# moc.net
KiCad netlist of a schematic drawn in EAGLE
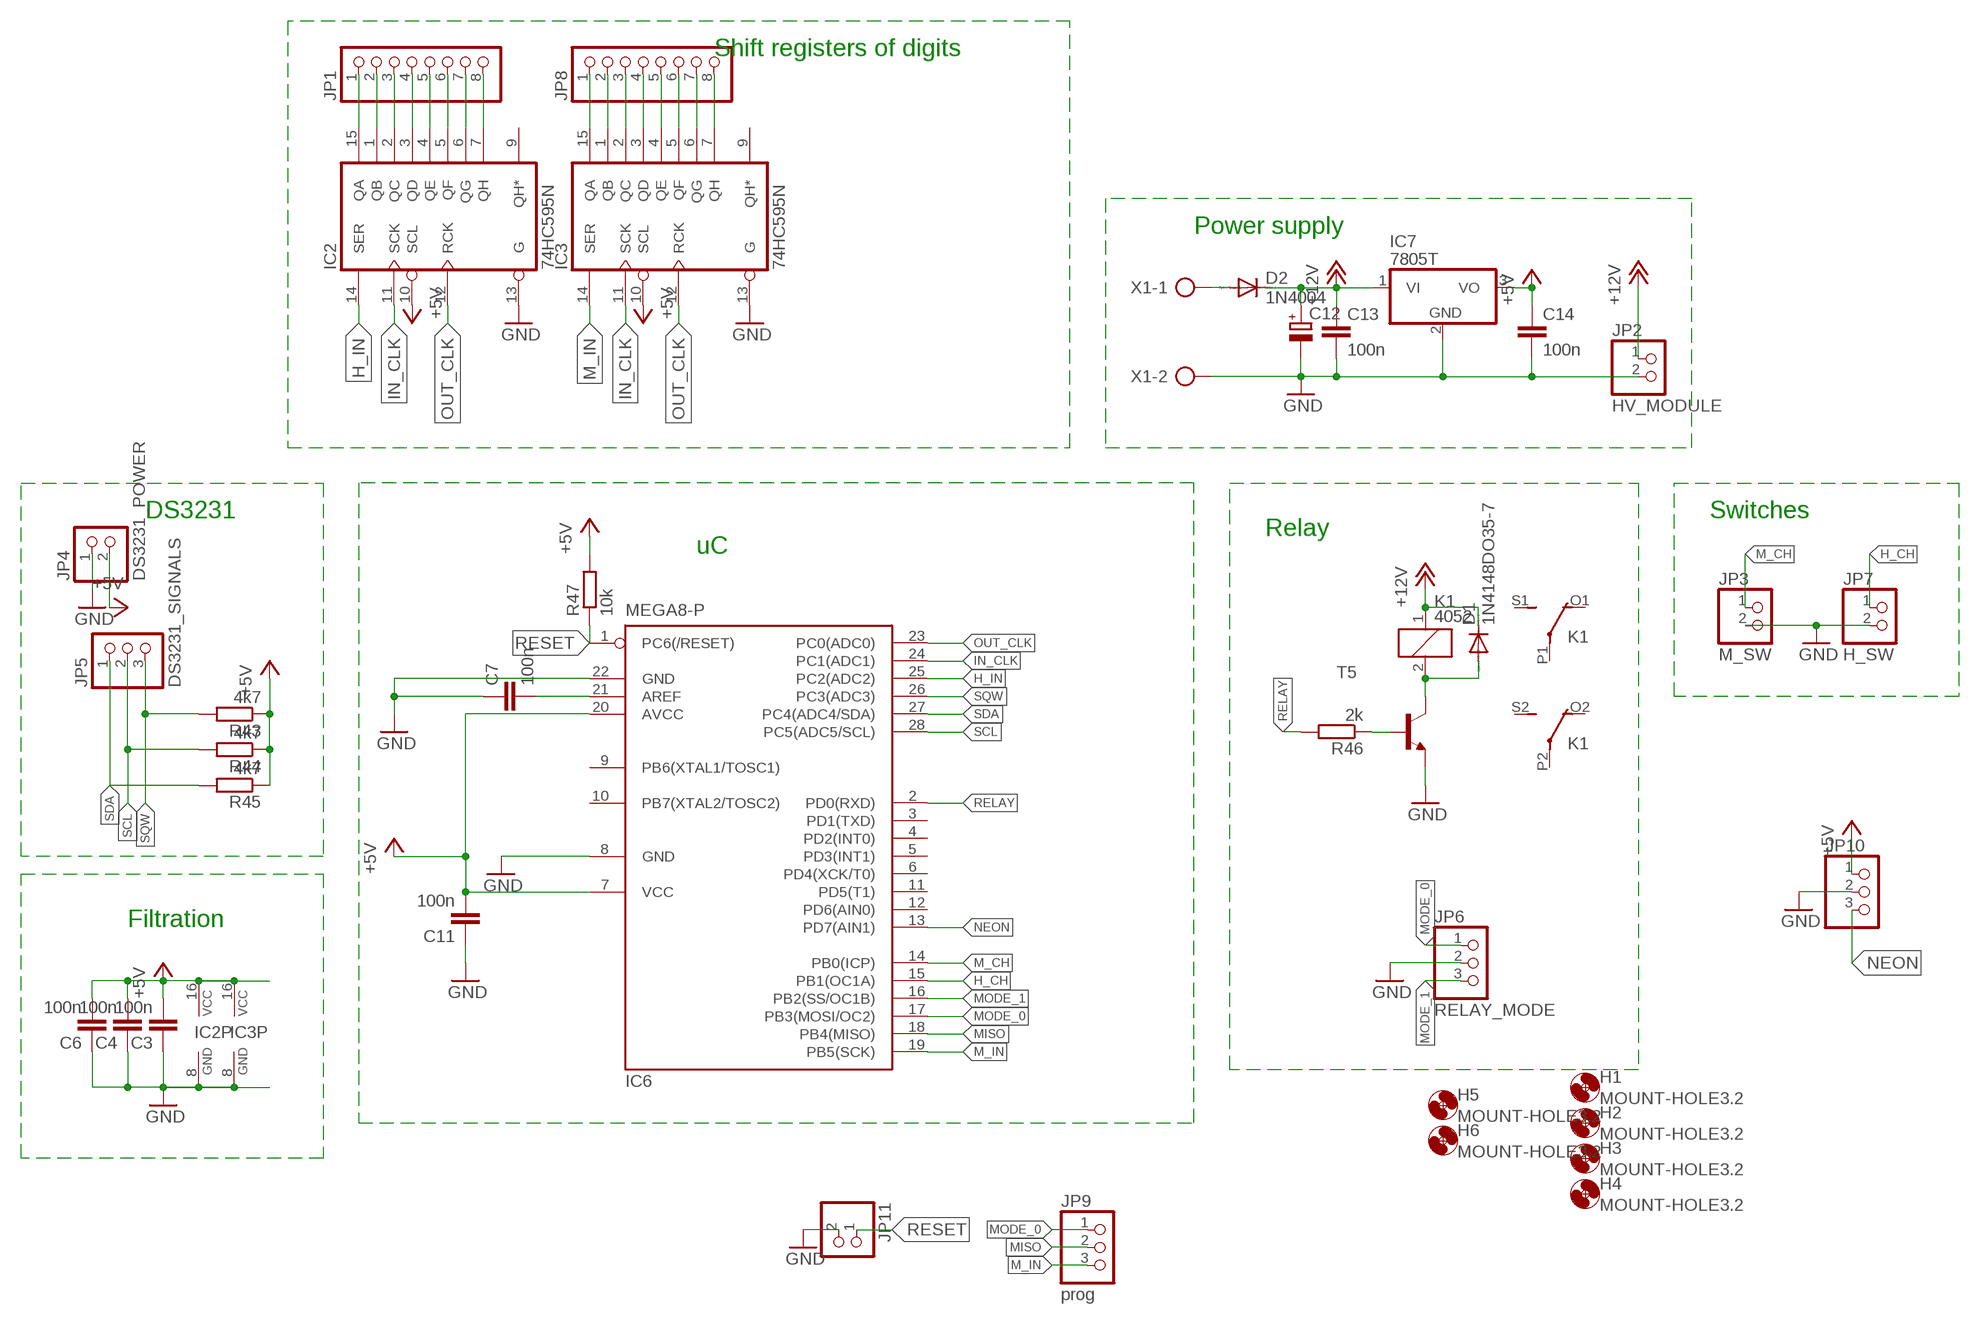
[diagram p0: schematic, sheet 1]

(export (version "E")
  (design (tool "Eeschema 10.0.6"))
  (components
    (comp (ref "C3")
      (value "100n")
      (footprint "eagle-import:C025-025X050")
      (libsource (lib "eagle-import") (part "C-EU025-025X050"))
    )
    (comp (ref "C4")
      (value "100n")
      (footprint "eagle-import:C025-025X050")
      (libsource (lib "eagle-import") (part "C-EU025-025X050"))
    )
    (comp (ref "C6")
      (value "100n")
      (footprint "eagle-import:C025-025X050")
      (libsource (lib "eagle-import") (part "C-EU025-025X050"))
    )
    (comp (ref "C7")
      (value "100n")
      (footprint "eagle-import:C025-025X050")
      (libsource (lib "eagle-import") (part "C-EU025-025X050"))
    )
    (comp (ref "C11")
      (value "100n")
      (footprint "eagle-import:C025-025X050")
      (libsource (lib "eagle-import") (part "C-EU025-025X050"))
    )
    (comp (ref "C12")
      (value "CPOL-EUE3.5-8")
      (footprint "eagle-import:E3,5-8")
      (libsource (lib "eagle-import") (part "CPOL-EUE3.5-8"))
    )
    (comp (ref "C13")
      (value "100n")
      (footprint "eagle-import:C025-025X050")
      (libsource (lib "eagle-import") (part "C-EU025-025X050"))
    )
    (comp (ref "C14")
      (value "100n")
      (footprint "eagle-import:C025-025X050")
      (libsource (lib "eagle-import") (part "C-EU025-025X050"))
    )
    (comp (ref "D1")
      (value "1N4148DO35-7")
      (footprint "eagle-import:DO35-7")
      (libsource (lib "eagle-import") (part "1N4148DO35-7"))
    )
    (comp (ref "D2")
      (value "1N4004")
      (footprint "eagle-import:DO41-10")
      (libsource (lib "eagle-import") (part "1N4004"))
    )
    (comp (ref "H1")
      (value "MOUNT-HOLE3.2")
      (footprint "eagle-import:3,2")
      (libsource (lib "eagle-import") (part "MOUNT-HOLE3.2"))
    )
    (comp (ref "H2")
      (value "MOUNT-HOLE3.2")
      (footprint "eagle-import:3,2")
      (libsource (lib "eagle-import") (part "MOUNT-HOLE3.2"))
    )
    (comp (ref "H3")
      (value "MOUNT-HOLE3.2")
      (footprint "eagle-import:3,2")
      (libsource (lib "eagle-import") (part "MOUNT-HOLE3.2"))
    )
    (comp (ref "H4")
      (value "MOUNT-HOLE3.2")
      (footprint "eagle-import:3,2")
      (libsource (lib "eagle-import") (part "MOUNT-HOLE3.2"))
    )
    (comp (ref "H5")
      (value "MOUNT-HOLE3.2")
      (footprint "eagle-import:3,2")
      (libsource (lib "eagle-import") (part "MOUNT-HOLE3.2"))
    )
    (comp (ref "H6")
      (value "MOUNT-HOLE3.2")
      (footprint "eagle-import:3,2")
      (libsource (lib "eagle-import") (part "MOUNT-HOLE3.2"))
    )
    (comp (ref "IC2")
      (value "74HC595N")
      (footprint "eagle-import:DIL16")
      (libsource (lib "eagle-import") (part "74595NHC"))
    )
    (comp (ref "IC3")
      (value "74HC595N")
      (footprint "eagle-import:DIL16")
      (libsource (lib "eagle-import") (part "74595NHC"))
    )
    (comp (ref "IC6")
      (value "MEGA8-P")
      (footprint "eagle-import:DIL28-3")
      (libsource (lib "eagle-import") (part "MEGA8-P"))
    )
    (comp (ref "IC7")
      (value "7805T")
      (footprint "eagle-import:TO220H")
      (libsource (lib "eagle-import") (part "78T05"))
    )
    (comp (ref "JP1")
      (value "PINHD-1X8")
      (footprint "eagle-import:1X08")
      (libsource (lib "eagle-import") (part "PINHD-1X8"))
    )
    (comp (ref "JP2")
      (value "HV_MODULE")
      (footprint "eagle-import:1X02")
      (libsource (lib "eagle-import") (part "PINHD-1X2"))
    )
    (comp (ref "JP3")
      (value "M_SW")
      (footprint "eagle-import:1X02")
      (libsource (lib "eagle-import") (part "PINHD-1X2"))
    )
    (comp (ref "JP4")
      (value "DS3231_POWER")
      (footprint "eagle-import:1X02")
      (libsource (lib "eagle-import") (part "PINHD-1X2"))
    )
    (comp (ref "JP5")
      (value "DS3231_SIGNALS")
      (footprint "eagle-import:1X03")
      (libsource (lib "eagle-import") (part "PINHD-1X3"))
    )
    (comp (ref "JP6")
      (value "RELAY_MODE")
      (footprint "eagle-import:1X03")
      (libsource (lib "eagle-import") (part "PINHD-1X3"))
    )
    (comp (ref "JP7")
      (value "H_SW")
      (footprint "eagle-import:1X02")
      (libsource (lib "eagle-import") (part "PINHD-1X2"))
    )
    (comp (ref "JP8")
      (value "PINHD-1X8")
      (footprint "eagle-import:1X08")
      (libsource (lib "eagle-import") (part "PINHD-1X8"))
    )
    (comp (ref "JP9")
      (value "prog")
      (footprint "eagle-import:1X03")
      (libsource (lib "eagle-import") (part "PINHD-1X3"))
    )
    (comp (ref "JP10")
      (value "PINHD-1X3")
      (footprint "eagle-import:1X03")
      (libsource (lib "eagle-import") (part "PINHD-1X3"))
    )
    (comp (ref "JP11")
      (value "PINHD-1X2/90")
      (footprint "eagle-import:1X02_90")
      (libsource (lib "eagle-import") (part "PINHD-1X2/90"))
    )
    (comp (ref "K1")
      (value "4052")
      (footprint "eagle-import:F4052")
      (libsource (lib "eagle-import") (part "4052"))
    )
    (comp (ref "R43")
      (value "4k7")
      (footprint "eagle-import:0207_10")
      (libsource (lib "eagle-import") (part "resistor_348_R-EU_0207/10"))
    )
    (comp (ref "R44")
      (value "4k7")
      (footprint "eagle-import:0207_10")
      (libsource (lib "eagle-import") (part "R-EU_0207/10"))
    )
    (comp (ref "R45")
      (value "4k7")
      (footprint "eagle-import:0207_10")
      (libsource (lib "eagle-import") (part "R-EU_0207/10"))
    )
    (comp (ref "R46")
      (value "2k")
      (footprint "eagle-import:0207_7")
      (libsource (lib "eagle-import") (part "resistor_348_R-EU_0207/7"))
    )
    (comp (ref "R47")
      (value "10k")
      (footprint "eagle-import:0207_10")
      (libsource (lib "eagle-import") (part "resistor_348_R-EU_0207/10"))
    )
    (comp (ref "T5")
      (value "BC337-16-NPN-TO92-CBE")
      (footprint "eagle-import:TO92-CBE")
      (libsource (lib "eagle-import") (part "-NPN-TO92-CBEBC337-16"))
    )
    (comp (ref "X1")
      (value "AK300/2")
      (footprint "eagle-import:AK300_2")
      (libsource (lib "eagle-import") (part "AK300/2"))
    )
  )
  (nets
    (net (code "1") (name "+5V") (class "Default")
      (node (ref "C11") (pin "2") (pinfunction "2_2") (pintype "passive"))
      (node (ref "C14") (pin "1") (pinfunction "1_1") (pintype "passive"))
      (node (ref "C3") (pin "2") (pinfunction "2_2") (pintype "passive"))
      (node (ref "C4") (pin "2") (pinfunction "2_2") (pintype "passive"))
      (node (ref "C6") (pin "2") (pinfunction "2_2") (pintype "passive"))
      (node (ref "IC2") (pin "10") (pinfunction "SCL_10") (pintype "input"))
      (node (ref "IC2") (pin "16") (pinfunction "VCC_16") (pintype "power_in"))
      (node (ref "IC3") (pin "10") (pinfunction "SCL_10") (pintype "input"))
      (node (ref "IC3") (pin "16") (pinfunction "VCC_16") (pintype "power_in"))
      (node (ref "IC6") (pin "20") (pinfunction "AVCC_20") (pintype "power_in"))
      (node (ref "IC6") (pin "7") (pinfunction "VCC_7") (pintype "power_in"))
      (node (ref "IC7") (pin "3") (pinfunction "VO_3") (pintype "passive"))
      (node (ref "JP10") (pin "1") (pinfunction "1_1") (pintype "passive"))
      (node (ref "JP4") (pin "2") (pinfunction "2_2") (pintype "passive"))
      (node (ref "R43") (pin "1") (pinfunction "1_1") (pintype "passive"))
      (node (ref "R44") (pin "1") (pinfunction "1_1") (pintype "passive"))
      (node (ref "R45") (pin "1") (pinfunction "1_1") (pintype "passive"))
      (node (ref "R47") (pin "2") (pinfunction "2_2") (pintype "passive"))
    )
    (net (code "2") (name "+12V") (class "Default")
      (node (ref "C12") (pin "+") (pinfunction "+_+") (pintype "passive"))
      (node (ref "C13") (pin "1") (pinfunction "1_1") (pintype "passive"))
      (node (ref "D1") (pin "C") (pinfunction "C_C") (pintype "passive"))
      (node (ref "D2") (pin "C") (pinfunction "C_C") (pintype "passive"))
      (node (ref "IC7") (pin "1") (pinfunction "VI_1") (pintype "input"))
      (node (ref "JP2") (pin "1") (pinfunction "1_1") (pintype "passive"))
      (node (ref "K1") (pin "1") (pinfunction "1_1") (pintype "passive"))
    )
    (net (code "3") (name "GND") (class "Default")
      (node (ref "C11") (pin "1") (pinfunction "1_1") (pintype "passive"))
      (node (ref "C12") (pin "-") (pinfunction "-_-") (pintype "passive"))
      (node (ref "C13") (pin "2") (pinfunction "2_2") (pintype "passive"))
      (node (ref "C14") (pin "2") (pinfunction "2_2") (pintype "passive"))
      (node (ref "C3") (pin "1") (pinfunction "1_1") (pintype "passive"))
      (node (ref "C4") (pin "1") (pinfunction "1_1") (pintype "passive"))
      (node (ref "C6") (pin "1") (pinfunction "1_1") (pintype "passive"))
      (node (ref "C7") (pin "1") (pinfunction "1_1") (pintype "passive"))
      (node (ref "IC2") (pin "13") (pinfunction "G_13") (pintype "input"))
      (node (ref "IC2") (pin "8") (pinfunction "GND_8") (pintype "power_in"))
      (node (ref "IC3") (pin "13") (pinfunction "G_13") (pintype "input"))
      (node (ref "IC3") (pin "8") (pinfunction "GND_8") (pintype "power_in"))
      (node (ref "IC6") (pin "22") (pinfunction "GND_22") (pintype "power_in"))
      (node (ref "IC6") (pin "8") (pinfunction "GND_8") (pintype "power_in"))
      (node (ref "IC7") (pin "2") (pinfunction "GND_2") (pintype "passive"))
      (node (ref "JP10") (pin "2") (pinfunction "2_2") (pintype "passive"))
      (node (ref "JP11") (pin "2") (pinfunction "2_2") (pintype "passive"))
      (node (ref "JP2") (pin "2") (pinfunction "2_2") (pintype "passive"))
      (node (ref "JP3") (pin "2") (pinfunction "2_2") (pintype "passive"))
      (node (ref "JP4") (pin "1") (pinfunction "1_1") (pintype "passive"))
      (node (ref "JP6") (pin "2") (pinfunction "2_2") (pintype "passive"))
      (node (ref "JP7") (pin "2") (pinfunction "2_2") (pintype "passive"))
      (node (ref "T5") (pin "E") (pinfunction "E_E") (pintype "passive"))
      (node (ref "X1") (pin "2") (pinfunction "KL_2") (pintype "passive"))
    )
    (net (code "4") (name "H_CH") (class "Default")
      (node (ref "IC6") (pin "15") (pinfunction "PB1(OC1A)_15") (pintype "bidirectional"))
      (node (ref "JP7") (pin "1") (pinfunction "1_1") (pintype "passive"))
    )
    (net (code "5") (name "H_IN") (class "Default")
      (node (ref "IC2") (pin "14") (pinfunction "SER_14") (pintype "input"))
      (node (ref "IC6") (pin "25") (pinfunction "PC2(ADC2)_25") (pintype "bidirectional"))
    )
    (net (code "6") (name "IN_CLK") (class "Default")
      (node (ref "IC2") (pin "11") (pinfunction "SCK_11") (pintype "input"))
      (node (ref "IC3") (pin "11") (pinfunction "SCK_11") (pintype "input"))
      (node (ref "IC6") (pin "24") (pinfunction "PC1(ADC1)_24") (pintype "bidirectional"))
    )
    (net (code "7") (name "MISO") (class "Default")
      (node (ref "IC6") (pin "18") (pinfunction "PB4(MISO)_18") (pintype "bidirectional"))
      (node (ref "JP9") (pin "2") (pinfunction "2_2") (pintype "passive"))
    )
    (net (code "8") (name "MODE_0") (class "Default")
      (node (ref "IC6") (pin "17") (pinfunction "PB3(MOSI/OC2)_17") (pintype "bidirectional"))
      (node (ref "JP6") (pin "1") (pinfunction "1_1") (pintype "passive"))
      (node (ref "JP9") (pin "1") (pinfunction "1_1") (pintype "passive"))
    )
    (net (code "9") (name "MODE_1") (class "Default")
      (node (ref "IC6") (pin "16") (pinfunction "PB2(SS/OC1B)_16") (pintype "bidirectional"))
      (node (ref "JP6") (pin "3") (pinfunction "3_3") (pintype "passive"))
    )
    (net (code "10") (name "M_CH") (class "Default")
      (node (ref "IC6") (pin "14") (pinfunction "PB0(ICP)_14") (pintype "bidirectional"))
      (node (ref "JP3") (pin "1") (pinfunction "1_1") (pintype "passive"))
    )
    (net (code "11") (name "M_IN") (class "Default")
      (node (ref "IC3") (pin "14") (pinfunction "SER_14") (pintype "input"))
      (node (ref "IC6") (pin "19") (pinfunction "PB5(SCK)_19") (pintype "bidirectional"))
      (node (ref "JP9") (pin "3") (pinfunction "3_3") (pintype "passive"))
    )
    (net (code "12") (name "NEON") (class "Default")
      (node (ref "IC6") (pin "13") (pinfunction "PD7(AIN1)_13") (pintype "bidirectional"))
      (node (ref "JP10") (pin "3") (pinfunction "3_3") (pintype "passive"))
    )
    (net (code "13") (name "Net-(D1-PadA)") (class "Default")
      (node (ref "D1") (pin "A") (pinfunction "A_A") (pintype "passive"))
      (node (ref "K1") (pin "2") (pinfunction "2_2") (pintype "passive"))
      (node (ref "T5") (pin "C") (pinfunction "C_C") (pintype "passive"))
    )
    (net (code "14") (name "Net-(IC2A-QA)") (class "Default")
      (node (ref "IC2") (pin "15") (pinfunction "QA_15") (pintype "tri_state"))
      (node (ref "JP1") (pin "1") (pinfunction "1_1") (pintype "passive"))
    )
    (net (code "15") (name "Net-(IC2A-QB)") (class "Default")
      (node (ref "IC2") (pin "1") (pinfunction "QB_1") (pintype "tri_state"))
      (node (ref "JP1") (pin "2") (pinfunction "2_2") (pintype "passive"))
    )
    (net (code "16") (name "Net-(IC2A-QC)") (class "Default")
      (node (ref "IC2") (pin "2") (pinfunction "QC_2") (pintype "tri_state"))
      (node (ref "JP1") (pin "3") (pinfunction "3_3") (pintype "passive"))
    )
    (net (code "17") (name "Net-(IC2A-QD)") (class "Default")
      (node (ref "IC2") (pin "3") (pinfunction "QD_3") (pintype "tri_state"))
      (node (ref "JP1") (pin "4") (pinfunction "4_4") (pintype "passive"))
    )
    (net (code "18") (name "Net-(IC2A-QE)") (class "Default")
      (node (ref "IC2") (pin "4") (pinfunction "QE_4") (pintype "tri_state"))
      (node (ref "JP1") (pin "5") (pinfunction "5_5") (pintype "passive"))
    )
    (net (code "19") (name "Net-(IC2A-QF)") (class "Default")
      (node (ref "IC2") (pin "5") (pinfunction "QF_5") (pintype "tri_state"))
      (node (ref "JP1") (pin "6") (pinfunction "6_6") (pintype "passive"))
    )
    (net (code "20") (name "Net-(IC2A-QG)") (class "Default")
      (node (ref "IC2") (pin "6") (pinfunction "QG_6") (pintype "tri_state"))
      (node (ref "JP1") (pin "7") (pinfunction "7_7") (pintype "passive"))
    )
    (net (code "21") (name "Net-(IC2A-QH)") (class "Default")
      (node (ref "IC2") (pin "7") (pinfunction "QH_7") (pintype "tri_state"))
      (node (ref "JP1") (pin "8") (pinfunction "8_8") (pintype "passive"))
    )
    (net (code "22") (name "Net-(IC3A-QA)") (class "Default")
      (node (ref "IC3") (pin "15") (pinfunction "QA_15") (pintype "tri_state"))
      (node (ref "JP8") (pin "1") (pinfunction "1_1") (pintype "passive"))
    )
    (net (code "23") (name "Net-(IC3A-QB)") (class "Default")
      (node (ref "IC3") (pin "1") (pinfunction "QB_1") (pintype "tri_state"))
      (node (ref "JP8") (pin "2") (pinfunction "2_2") (pintype "passive"))
    )
    (net (code "24") (name "Net-(IC3A-QC)") (class "Default")
      (node (ref "IC3") (pin "2") (pinfunction "QC_2") (pintype "tri_state"))
      (node (ref "JP8") (pin "3") (pinfunction "3_3") (pintype "passive"))
    )
    (net (code "25") (name "Net-(IC3A-QD)") (class "Default")
      (node (ref "IC3") (pin "3") (pinfunction "QD_3") (pintype "tri_state"))
      (node (ref "JP8") (pin "4") (pinfunction "4_4") (pintype "passive"))
    )
    (net (code "26") (name "Net-(IC3A-QE)") (class "Default")
      (node (ref "IC3") (pin "4") (pinfunction "QE_4") (pintype "tri_state"))
      (node (ref "JP8") (pin "5") (pinfunction "5_5") (pintype "passive"))
    )
    (net (code "27") (name "Net-(IC3A-QF)") (class "Default")
      (node (ref "IC3") (pin "5") (pinfunction "QF_5") (pintype "tri_state"))
      (node (ref "JP8") (pin "6") (pinfunction "6_6") (pintype "passive"))
    )
    (net (code "28") (name "Net-(IC3A-QG)") (class "Default")
      (node (ref "IC3") (pin "6") (pinfunction "QG_6") (pintype "tri_state"))
      (node (ref "JP8") (pin "7") (pinfunction "7_7") (pintype "passive"))
    )
    (net (code "29") (name "Net-(IC3A-QH)") (class "Default")
      (node (ref "IC3") (pin "7") (pinfunction "QH_7") (pintype "tri_state"))
      (node (ref "JP8") (pin "8") (pinfunction "8_8") (pintype "passive"))
    )
    (net (code "30") (name "Net-(IC6-AREF)") (class "Default")
      (node (ref "C7") (pin "2") (pinfunction "2_2") (pintype "passive"))
      (node (ref "IC6") (pin "21") (pinfunction "AREF_21") (pintype "passive"))
    )
    (net (code "31") (name "Net-(R46-Pad1)") (class "Default")
      (node (ref "R46") (pin "1") (pinfunction "1_1") (pintype "passive"))
      (node (ref "T5") (pin "B") (pinfunction "B_B") (pintype "passive"))
    )
    (net (code "32") (name "Net-(X1A-KL)") (class "Default")
      (node (ref "D2") (pin "A") (pinfunction "A_A") (pintype "passive"))
      (node (ref "X1") (pin "1") (pinfunction "KL_1") (pintype "passive"))
    )
    (net (code "33") (name "OUT_CLK") (class "Default")
      (node (ref "IC2") (pin "12") (pinfunction "RCK_12") (pintype "input"))
      (node (ref "IC3") (pin "12") (pinfunction "RCK_12") (pintype "input"))
      (node (ref "IC6") (pin "23") (pinfunction "PC0(ADC0)_23") (pintype "bidirectional"))
    )
    (net (code "34") (name "RELAY") (class "Default")
      (node (ref "IC6") (pin "2") (pinfunction "PD0(RXD)_2") (pintype "bidirectional"))
      (node (ref "R46") (pin "2") (pinfunction "2_2") (pintype "passive"))
    )
    (net (code "35") (name "RESET") (class "Default")
      (node (ref "IC6") (pin "1") (pinfunction "PC6(/RESET)_1") (pintype "bidirectional"))
      (node (ref "JP11") (pin "1") (pinfunction "1_1") (pintype "passive"))
      (node (ref "R47") (pin "1") (pinfunction "1_1") (pintype "passive"))
    )
    (net (code "36") (name "SCL") (class "Default")
      (node (ref "IC6") (pin "28") (pinfunction "PC5(ADC5/SCL)_28") (pintype "bidirectional"))
      (node (ref "JP5") (pin "2") (pinfunction "2_2") (pintype "passive"))
      (node (ref "R44") (pin "2") (pinfunction "2_2") (pintype "passive"))
    )
    (net (code "37") (name "SDA") (class "Default")
      (node (ref "IC6") (pin "27") (pinfunction "PC4(ADC4/SDA)_27") (pintype "bidirectional"))
      (node (ref "JP5") (pin "1") (pinfunction "1_1") (pintype "passive"))
      (node (ref "R45") (pin "2") (pinfunction "2_2") (pintype "passive"))
    )
    (net (code "38") (name "SQW") (class "Default")
      (node (ref "IC6") (pin "26") (pinfunction "PC3(ADC3)_26") (pintype "bidirectional"))
      (node (ref "JP5") (pin "3") (pinfunction "3_3") (pintype "passive"))
      (node (ref "R43") (pin "2") (pinfunction "2_2") (pintype "passive"))
    )
    (net (code "39") (name "unconnected-(IC2A-QH*-Pad9)") (class "Default")
      (node (ref "IC2") (pin "9") (pinfunction "QH*_9") (pintype "tri_state"))
    )
    (net (code "40") (name "unconnected-(IC3A-QH*-Pad9)") (class "Default")
      (node (ref "IC3") (pin "9") (pinfunction "QH*_9") (pintype "tri_state"))
    )
    (net (code "41") (name "unconnected-(IC6-PB6(XTAL1{slash}TOSC1)-Pad9)") (class "Default")
      (node (ref "IC6") (pin "9") (pinfunction "PB6(XTAL1/TOSC1)_9") (pintype "bidirectional"))
    )
    (net (code "42") (name "unconnected-(IC6-PB7(XTAL2{slash}TOSC2)-Pad10)") (class "Default")
      (node (ref "IC6") (pin "10") (pinfunction "PB7(XTAL2/TOSC2)_10") (pintype "bidirectional"))
    )
    (net (code "43") (name "unconnected-(IC6-PD1(TXD)-Pad3)") (class "Default")
      (node (ref "IC6") (pin "3") (pinfunction "PD1(TXD)_3") (pintype "bidirectional"))
    )
    (net (code "44") (name "unconnected-(IC6-PD2(INT0)-Pad4)") (class "Default")
      (node (ref "IC6") (pin "4") (pinfunction "PD2(INT0)_4") (pintype "bidirectional"))
    )
    (net (code "45") (name "unconnected-(IC6-PD3(INT1)-Pad5)") (class "Default")
      (node (ref "IC6") (pin "5") (pinfunction "PD3(INT1)_5") (pintype "bidirectional"))
    )
    (net (code "46") (name "unconnected-(IC6-PD4(XCK{slash}T0)-Pad6)") (class "Default")
      (node (ref "IC6") (pin "6") (pinfunction "PD4(XCK/T0)_6") (pintype "bidirectional"))
    )
    (net (code "47") (name "unconnected-(IC6-PD5(T1)-Pad11)") (class "Default")
      (node (ref "IC6") (pin "11") (pinfunction "PD5(T1)_11") (pintype "bidirectional"))
    )
    (net (code "48") (name "unconnected-(IC6-PD6(AIN0)-Pad12)") (class "Default")
      (node (ref "IC6") (pin "12") (pinfunction "PD6(AIN0)_12") (pintype "bidirectional"))
    )
    (net (code "49") (name "unconnected-(K1B-O-PadO1)") (class "Default")
      (node (ref "K1") (pin "O1") (pinfunction "O_O1") (pintype "passive"))
    )
    (net (code "50") (name "unconnected-(K1B-P-PadP1)") (class "Default")
      (node (ref "K1") (pin "P1") (pinfunction "P_P1") (pintype "passive"))
    )
    (net (code "51") (name "unconnected-(K1B-S-PadS1)") (class "Default")
      (node (ref "K1") (pin "S1") (pinfunction "S_S1") (pintype "passive"))
    )
    (net (code "52") (name "unconnected-(K1C-O-PadO2)") (class "Default")
      (node (ref "K1") (pin "O2") (pinfunction "O_O2") (pintype "passive"))
    )
    (net (code "53") (name "unconnected-(K1C-P-PadP2)") (class "Default")
      (node (ref "K1") (pin "P2") (pinfunction "P_P2") (pintype "passive"))
    )
    (net (code "54") (name "unconnected-(K1C-S-PadS2)") (class "Default")
      (node (ref "K1") (pin "S2") (pinfunction "S_S2") (pintype "passive"))
    )
  )
)
